# Data_Receiver.net
KiCad netlist of a schematic drawn in Altium Designer
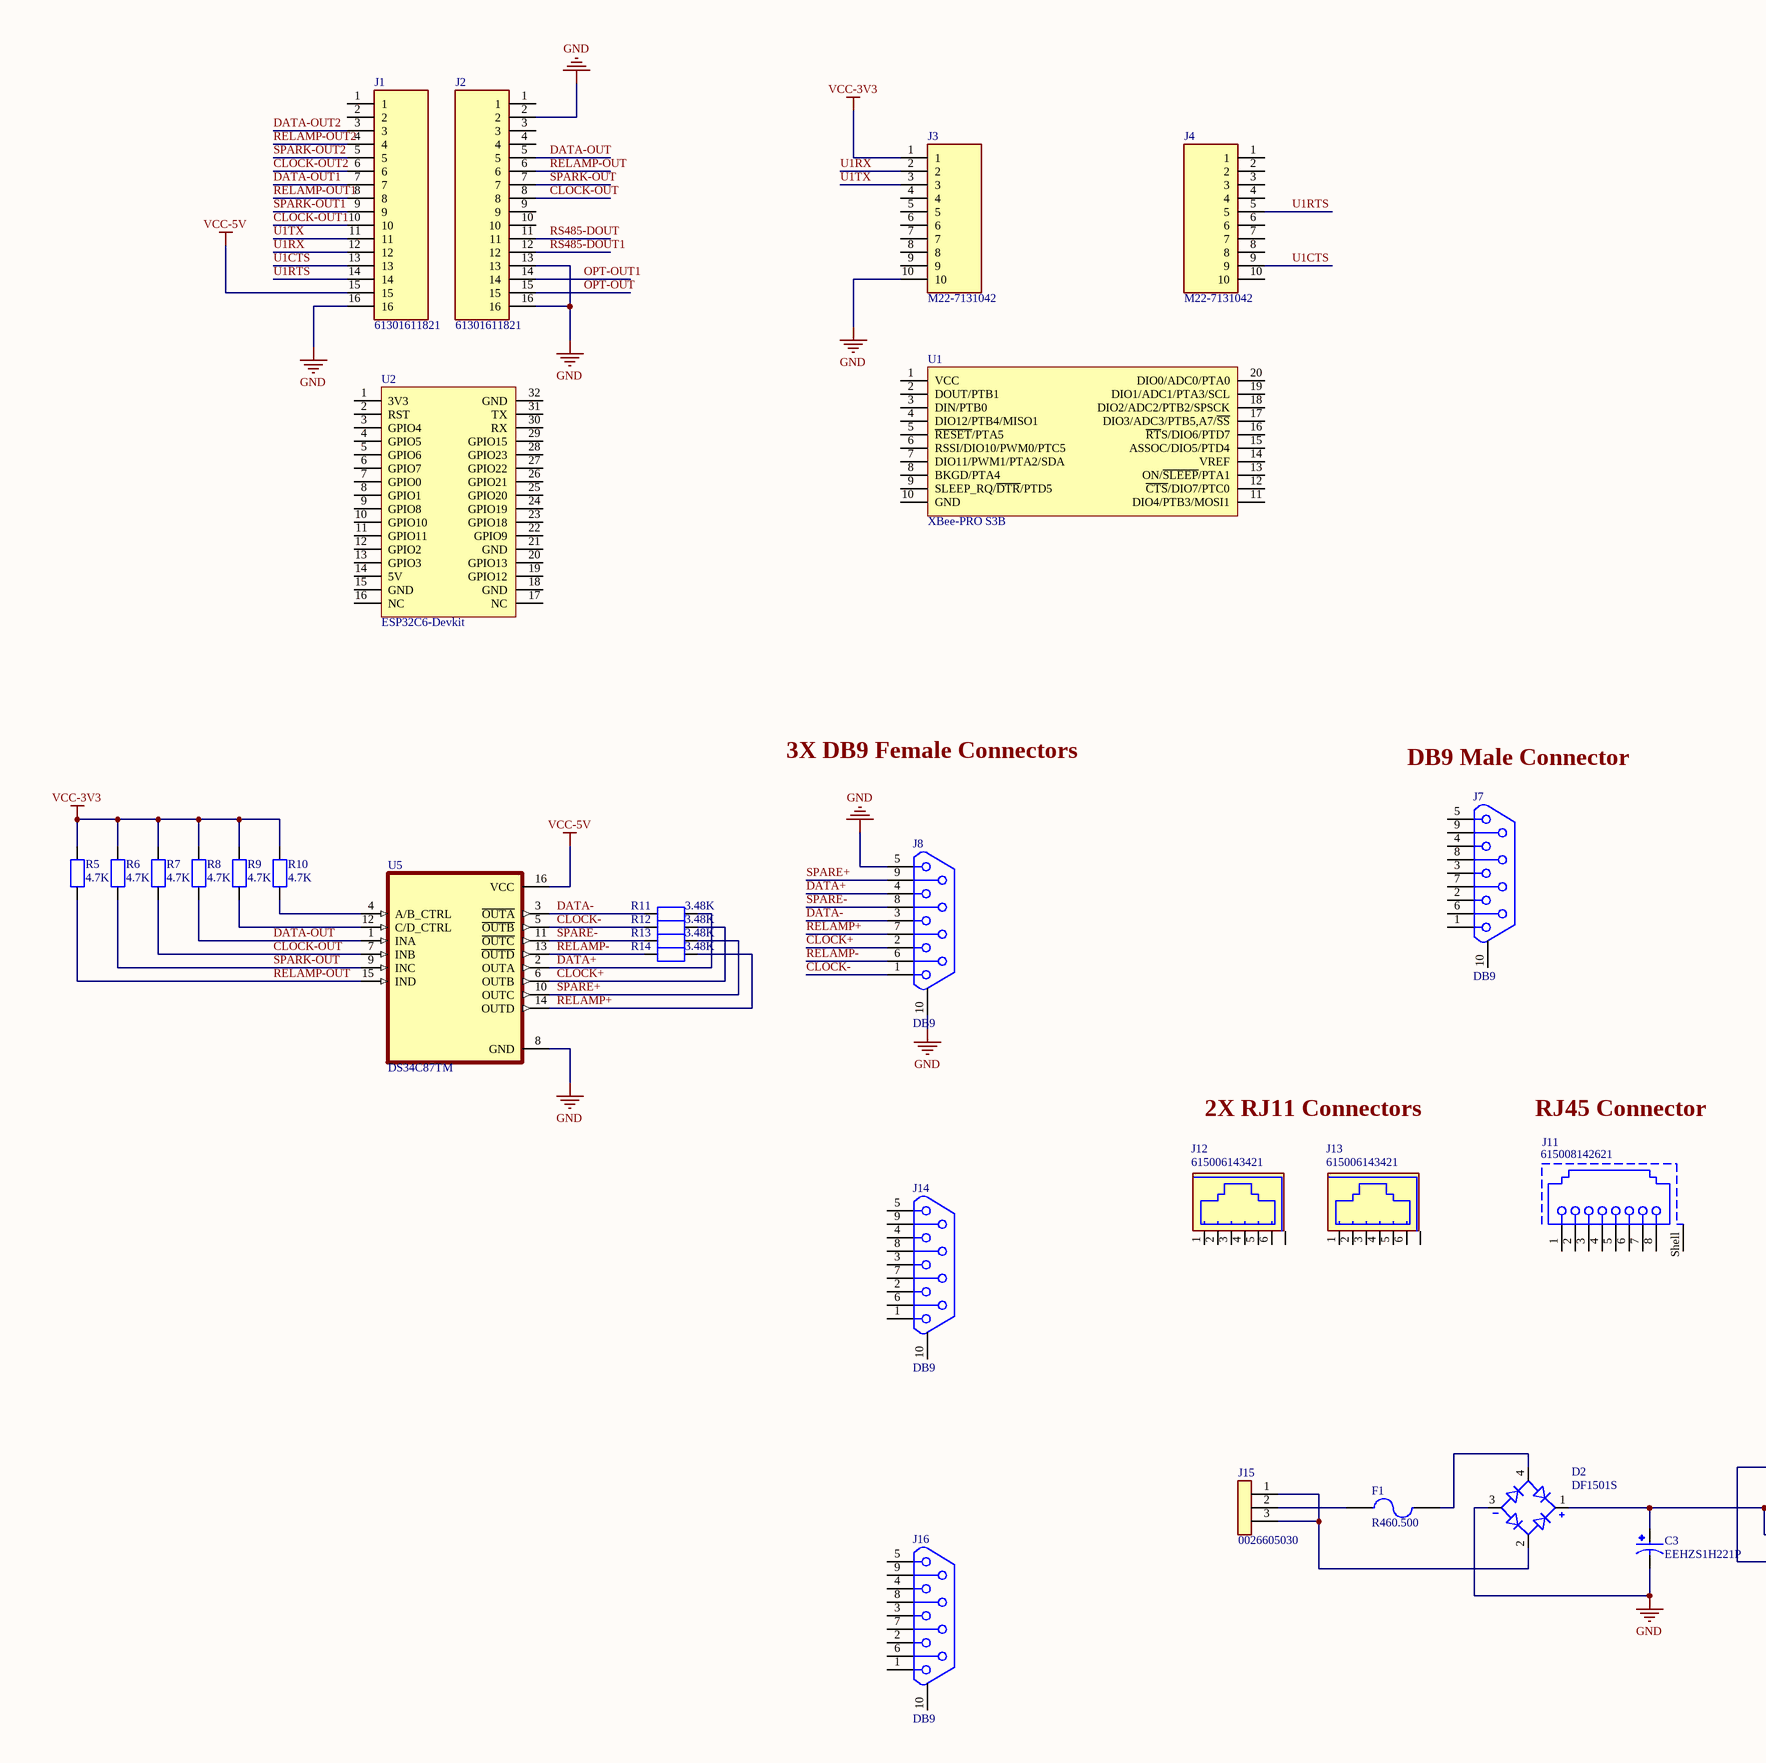
[diagram p0: Data Receiver.SchDoc, left]
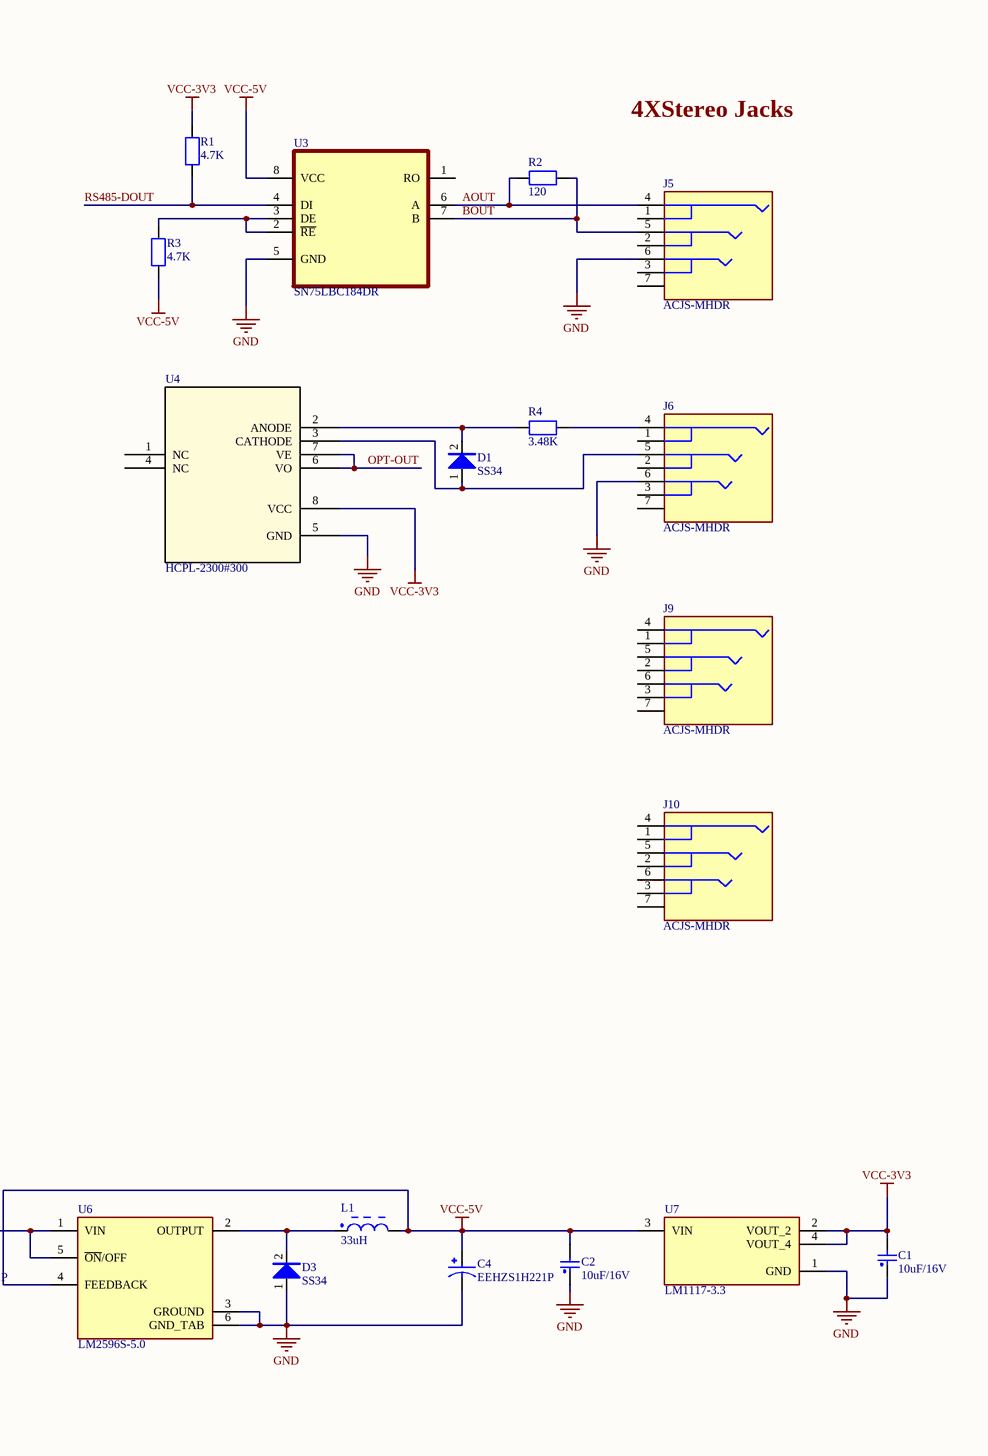
[diagram p1: Data Receiver.SchDoc, right]

(export (version "E")
  (design (tool "Eeschema 10.0.6"))
  (components
    (comp (ref "C1")
      (value "10uF/16V")
      (footprint "CAP-0805")
      (description "Capacitor")
      (fields
        (field (name "MANUFACTURER") "Samsung Electro-Mechanics")
        (field (name "MANUFACTURER PART NUMBER") "CL10B104KO8NNNC")
      )
      (libsource (lib "Data Receiver") (part "CAP"))
    )
    (comp (ref "C2")
      (value "10uF/16V")
      (footprint "CAP-0805")
      (description "Capacitor")
      (fields
        (field (name "MANUFACTURER") "Samsung Electro-Mechanics")
        (field (name "MANUFACTURER PART NUMBER") "CL10B104KO8NNNC")
      )
      (libsource (lib "Data Receiver") (part "CAP"))
    )
    (comp (ref "C3")
      (value "EEHZS1H221P")
      (footprint "CAP_EEHZS1H221P")
      (description "Aluminium Organic Polymer Capacitors 50VDC 220uF 125degC Hybrid Cap AEC-Q200")
      (fields
        (field (name "MANUFACTURER") "Panasonic")
        (field (name "MANUFACTURER PART NUMBER") "EEH-ZS1H221P")
      )
      (libsource (lib "Data Receiver") (part "EEHZS1H221P"))
    )
    (comp (ref "C4")
      (value "EEHZS1H221P")
      (footprint "CAP_EEHZS1H221P")
      (description "Aluminium Organic Polymer Capacitors 50VDC 220uF 125degC Hybrid Cap AEC-Q200")
      (fields
        (field (name "MANUFACTURER") "Panasonic")
        (field (name "MANUFACTURER PART NUMBER") "EEH-ZS1H221P")
      )
      (libsource (lib "Data Receiver") (part "EEHZS1H221P"))
    )
    (comp (ref "D1")
      (value "SS34")
      (footprint "SMA")
      (description "Diode 40 V 3A Surface Mount SMA")
      (fields (field (name "MANUFACTURER") "Taiwan Semiconductor"))
      (libsource (lib "Data Receiver") (part "DIODE"))
    )
    (comp (ref "D2")
      (value "DF1501S")
      (footprint "SOT520P1040X293-4N")
      (description "Bridge Rectifier Single Phase Standard 100V Surface Mount DFS")
      (fields (field (name "MANUFACTURER") "Diodes Incorporated"))
      (libsource (lib "Data Receiver") (part "DF1501S"))
    )
    (comp (ref "D3")
      (value "SS34")
      (footprint "SMA")
      (description "Diode 40 V 3A Surface Mount SMA")
      (fields (field (name "MANUFACTURER") "Taiwan Semiconductor"))
      (libsource (lib "Data Receiver") (part "DIODE"))
    )
    (comp (ref "F1")
      (value "R460.500")
      (footprint "CAPM7243X30N")
      (description "500 mA 125 V AC 125 V DC Fuse Board Mount (Cartridge Style Excluded) Surface Mount 2-SMD, J-Lead")
      (fields
        (field (name "MANUFACTURER") "Littelfuse Inc.")
        (field (name "MANUFACTURER PART NUMBER") "0460.500ER")
      )
      (libsource (lib "Data Receiver") (part "Fuse 2"))
    )
    (comp (ref "J1")
      (value "61301611821")
      (footprint "61301611821")
      (description "16 Position Header Connector 0.100\" (2.54mm) Through Hole Gold")
      (fields (field (name "MANUFACTURER") "Wurth Elektronik"))
      (libsource (lib "") (part "61301611821_1"))
    )
    (comp (ref "J2")
      (value "61301611821")
      (footprint "61301611821")
      (description "16 Position Header Connector 0.100\" (2.54mm) Through Hole Gold")
      (fields (field (name "MANUFACTURER") "Wurth Elektronik"))
      (libsource (lib "Data Receiver") (part "61301611821"))
    )
    (comp (ref "J3")
      (value "M22-7131042")
      (footprint "M22-7131042")
      (fields (field (name "MANUFACTURER") "Harwin"))
      (libsource (lib "Data Receiver") (part "M22-7131042"))
    )
    (comp (ref "J4")
      (value "M22-7131042")
      (footprint "M22-7131042")
      (fields (field (name "MANUFACTURER") "Harwin"))
      (libsource (lib "") (part "M22-7131042_1"))
    )
    (comp (ref "J5")
      (value "ACJS-MHDR")
      (footprint "ACJSMHDR")
      (description "Phone Connectors 1/4\" STEREO SWITCHED REAN")
      (fields (field (name "MANUFACTURER") "Amphenol Audio"))
      (libsource (lib "Data Receiver") (part "ACJS-MHDR"))
    )
    (comp (ref "J6")
      (value "ACJS-MHDR")
      (footprint "ACJSMHDR")
      (description "Phone Connectors 1/4\" STEREO SWITCHED REAN")
      (fields (field (name "MANUFACTURER") "Amphenol Audio"))
      (libsource (lib "Data Receiver") (part "ACJS-MHDR"))
    )
    (comp (ref "J7")
      (value "DB9")
      (footprint "DB9/F_A")
      (description "9 Position D-Sub Receptacle, Male Sockets Connector")
      (fields
        (field (name "MANUFACTURER") "Würth Elektronik")
        (field (name "MANUFACTURER PART NUMBER") "618009231321")
      )
      (libsource (lib "Data Receiver") (part "DB9_Male"))
    )
    (comp (ref "J8")
      (value "DB9")
      (footprint "DB9/S_A")
      (description "9 Position D-Sub Receptacle, Female Sockets Connector")
      (fields
        (field (name "MANUFACTURER") "Würth Elektronik")
        (field (name "MANUFACTURER PART NUMBER") "618009231321")
      )
      (libsource (lib "Data Receiver") (part "DB9"))
    )
    (comp (ref "J9")
      (value "ACJS-MHDR")
      (footprint "ACJSMHDR")
      (description "Phone Connectors 1/4\" STEREO SWITCHED REAN")
      (fields (field (name "MANUFACTURER") "Amphenol Audio"))
      (libsource (lib "Data Receiver") (part "ACJS-MHDR"))
    )
    (comp (ref "J10")
      (value "ACJS-MHDR")
      (footprint "ACJSMHDR")
      (description "Phone Connectors 1/4\" STEREO SWITCHED REAN")
      (fields (field (name "MANUFACTURER") "Amphenol Audio"))
      (libsource (lib "Data Receiver") (part "ACJS-MHDR"))
    )
    (comp (ref "J11")
      (value "615008142621")
      (footprint "615008142621")
      (description "WR-MJ Modular Jack THT Horizontal Shielded Rear Grounding Post 8P8C Tab Down")
      (fields (field (name "MANUFACTURER") "Wurth Elektronik"))
      (libsource (lib "Data Receiver") (part "615008142621"))
    )
    (comp (ref "J12")
      (value "615006143421")
      (footprint "615006143421")
      (description "Modular Connectors / Ethernet Connectors WR-COM Modular Jack Horztl 1.5A")
      (fields (field (name "MANUFACTURER") "Wurth Elektronik"))
      (libsource (lib "615006143421") (part "615006143421"))
    )
    (comp (ref "J13")
      (value "615006143421")
      (footprint "615006143421")
      (description "Modular Connectors / Ethernet Connectors WR-COM Modular Jack Horztl 1.5A")
      (fields (field (name "MANUFACTURER") "Wurth Elektronik"))
      (libsource (lib "615006143421") (part "615006143421"))
    )
    (comp (ref "J14")
      (value "DB9")
      (footprint "DB9/S_A")
      (description "9 Position D-Sub Receptacle, Female Sockets Connector")
      (fields
        (field (name "MANUFACTURER") "Würth Elektronik")
        (field (name "MANUFACTURER PART NUMBER") "618009231321")
      )
      (libsource (lib "Data Receiver") (part "DB9"))
    )
    (comp (ref "J15")
      (value "0026605030")
      (footprint "0026605030")
      (description "Connector Header Through Hole, Right Angle 3 position 0.156\" (3.96mm)")
      (fields (field (name "MANUFACTURER") "Molex"))
      (libsource (lib "Data Receiver") (part "HEADER3"))
    )
    (comp (ref "J16")
      (value "DB9")
      (footprint "DB9/S_A")
      (description "9 Position D-Sub Receptacle, Female Sockets Connector")
      (fields
        (field (name "MANUFACTURER") "Würth Elektronik")
        (field (name "MANUFACTURER PART NUMBER") "618009231321")
      )
      (libsource (lib "Data Receiver") (part "DB9"))
    )
    (comp (ref "L1")
      (value "33uH")
      (footprint "IND_BOURNS_SRR12")
      (description "33 µH Shielded Drum Core, Wirewound Inductor 3.5 A 57mOhm Max Nonstandard")
      (fields
        (field (name "MANUFACTURER") "Bourns Inc.")
        (field (name "MANUFACTURER PART NUMBER") "SRR1280-330M")
      )
      (libsource (lib "Data Receiver") (part "INDUCTOR"))
    )
    (comp (ref "R1")
      (value "4.7K")
      (footprint "R0603")
      (description "4.7 kOhms ±1% 0.1W, 1/10W Chip Resistor 0603 (1608 Metric) Moisture Resistant Thick Film")
      (fields
        (field (name "MANUFACTURER") "Yageo")
        (field (name "MANUFACTURER PART NUMBER") "RC0603FR-074K7L")
      )
      (libsource (lib "Data Receiver") (part "4.7K Ohms ±1% 0.1W"))
    )
    (comp (ref "R2")
      (value "120")
      (footprint "R0603")
      (description "120 Ohms ±1% 0.1W, 1/10W Chip Resistor 0603 (1608 Metric) Moisture Resistant Thick Film")
      (fields
        (field (name "MANUFACTURER") "Yageo")
        (field (name "MANUFACTURER PART NUMBER") "RC0603FR-07120RL")
      )
      (libsource (lib "Data Receiver") (part "120 Ohms ±1% 0.1W"))
    )
    (comp (ref "R3")
      (value "4.7K")
      (footprint "R0603")
      (description "4.7 kOhms ±1% 0.1W, 1/10W Chip Resistor 0603 (1608 Metric) Moisture Resistant Thick Film")
      (fields
        (field (name "MANUFACTURER") "Yageo")
        (field (name "MANUFACTURER PART NUMBER") "RC0603FR-074K7L")
      )
      (libsource (lib "Data Receiver") (part "4.7K Ohms ±1% 0.1W"))
    )
    (comp (ref "R4")
      (value "3.48K")
      (footprint "R0603")
      (description "3.48 kOhms ±1% 0.1W, 1/10W Chip Resistor 0603 (1608 Metric) Moisture Resistant Thick Film")
      (fields
        (field (name "MANUFACTURER") "Yageo")
        (field (name "MANUFACTURER PART NUMBER") "RC0603FR-073K48L")
      )
      (libsource (lib "Data Receiver") (part "3.48K Ohms ±1% 0.1W"))
    )
    (comp (ref "R5")
      (value "4.7K")
      (footprint "R0603")
      (description "4.7 kOhms ±1% 0.1W, 1/10W Chip Resistor 0603 (1608 Metric) Moisture Resistant Thick Film")
      (fields
        (field (name "MANUFACTURER") "Yageo")
        (field (name "MANUFACTURER PART NUMBER") "RC0603FR-074K7L")
      )
      (libsource (lib "Data Receiver") (part "4.7K Ohms ±1% 0.1W"))
    )
    (comp (ref "R6")
      (value "4.7K")
      (footprint "R0603")
      (description "4.7 kOhms ±1% 0.1W, 1/10W Chip Resistor 0603 (1608 Metric) Moisture Resistant Thick Film")
      (fields
        (field (name "MANUFACTURER") "Yageo")
        (field (name "MANUFACTURER PART NUMBER") "RC0603FR-074K7L")
      )
      (libsource (lib "Data Receiver") (part "4.7K Ohms ±1% 0.1W"))
    )
    (comp (ref "R7")
      (value "4.7K")
      (footprint "R0603")
      (description "4.7 kOhms ±1% 0.1W, 1/10W Chip Resistor 0603 (1608 Metric) Moisture Resistant Thick Film")
      (fields
        (field (name "MANUFACTURER") "Yageo")
        (field (name "MANUFACTURER PART NUMBER") "RC0603FR-074K7L")
      )
      (libsource (lib "Data Receiver") (part "4.7K Ohms ±1% 0.1W"))
    )
    (comp (ref "R8")
      (value "4.7K")
      (footprint "R0603")
      (description "4.7 kOhms ±1% 0.1W, 1/10W Chip Resistor 0603 (1608 Metric) Moisture Resistant Thick Film")
      (fields
        (field (name "MANUFACTURER") "Yageo")
        (field (name "MANUFACTURER PART NUMBER") "RC0603FR-074K7L")
      )
      (libsource (lib "Data Receiver") (part "4.7K Ohms ±1% 0.1W"))
    )
    (comp (ref "R9")
      (value "4.7K")
      (footprint "R0603")
      (description "4.7 kOhms ±1% 0.1W, 1/10W Chip Resistor 0603 (1608 Metric) Moisture Resistant Thick Film")
      (fields
        (field (name "MANUFACTURER") "Yageo")
        (field (name "MANUFACTURER PART NUMBER") "RC0603FR-074K7L")
      )
      (libsource (lib "Data Receiver") (part "4.7K Ohms ±1% 0.1W"))
    )
    (comp (ref "R10")
      (value "4.7K")
      (footprint "R0603")
      (description "4.7 kOhms ±1% 0.1W, 1/10W Chip Resistor 0603 (1608 Metric) Moisture Resistant Thick Film")
      (fields
        (field (name "MANUFACTURER") "Yageo")
        (field (name "MANUFACTURER PART NUMBER") "RC0603FR-074K7L")
      )
      (libsource (lib "Data Receiver") (part "4.7K Ohms ±1% 0.1W"))
    )
    (comp (ref "R11")
      (value "3.48K")
      (footprint "R0603")
      (description "3.48 kOhms ±1% 0.1W, 1/10W Chip Resistor 0603 (1608 Metric) Moisture Resistant Thick Film")
      (fields
        (field (name "MANUFACTURER") "Yageo")
        (field (name "MANUFACTURER PART NUMBER") "RC0603FR-073K48L")
      )
      (libsource (lib "Data Receiver") (part "3.48K Ohms ±1% 0.1W"))
    )
    (comp (ref "R12")
      (value "3.48K")
      (footprint "R0603")
      (description "3.48 kOhms ±1% 0.1W, 1/10W Chip Resistor 0603 (1608 Metric) Moisture Resistant Thick Film")
      (fields
        (field (name "MANUFACTURER") "Yageo")
        (field (name "MANUFACTURER PART NUMBER") "RC0603FR-073K48L")
      )
      (libsource (lib "Data Receiver") (part "3.48K Ohms ±1% 0.1W"))
    )
    (comp (ref "R13")
      (value "3.48K")
      (footprint "R0603")
      (description "3.48 kOhms ±1% 0.1W, 1/10W Chip Resistor 0603 (1608 Metric) Moisture Resistant Thick Film")
      (fields
        (field (name "MANUFACTURER") "Yageo")
        (field (name "MANUFACTURER PART NUMBER") "RC0603FR-073K48L")
      )
      (libsource (lib "Data Receiver") (part "3.48K Ohms ±1% 0.1W"))
    )
    (comp (ref "R14")
      (value "3.48K")
      (footprint "R0603")
      (description "3.48 kOhms ±1% 0.1W, 1/10W Chip Resistor 0603 (1608 Metric) Moisture Resistant Thick Film")
      (fields
        (field (name "MANUFACTURER") "Yageo")
        (field (name "MANUFACTURER PART NUMBER") "RC0603FR-073K48L")
      )
      (libsource (lib "Data Receiver") (part "3.48K Ohms ±1% 0.1W"))
    )
    (comp (ref "U1")
      (value "XBee-PRO S3B")
      (footprint "XBEE(MMS-110-02-L-SV-K-TR)")
      (description "General ISM < 1GHz Transceiver Module 920MHz Antenna Not Included, RP-SMA Through Hole")
      (fields (field (name "MANUFACTURER") "DIGI") (field (name "MANUFACTURER PART NUMBER") "XBP9B-XCST-022"))
      (libsource (lib "Data Receiver") (part "XBee-PRO S3B"))
    )
    (comp (ref "U2")
      (value "ESP32C6-Devkit")
      (footprint "ESP32-C6-Devkit")
      (description "ESP32-C6-MINI-1 Transceiver; Bluetooth® 5 2.4GHz Evaluation Board")
      (fields
        (field (name "MANUFACTURER") "Espressif Systems")
        (field (name "MANUFACTURER PART NUMBER") "ESP32-C6-DevKitM-1-N4")
      )
      (libsource (lib "Data Receiver") (part "ESP32C6-Devkit"))
    )
    (comp (ref "U3")
      (value "SN75LBC184DR")
      (footprint "SOIC127P620X175-8N")
      (description "Enhanced Low Power Half-Duplex RS-485 Transceivers")
      (fields
        (field (name "MANUFACTURER") "MaxLinear, Inc.")
        (field (name "MANUFACTURER PART NUMBER") "SP485EEN-L")
      )
      (libsource (lib "Data Receiver") (part "SP485EEN-L"))
    )
    (comp (ref "U4")
      (value "HCPL-2300#300")
      (footprint "SOP254P960X420-8N")
      (fields (field (name "MANUFACTURER") "Broadcom Limited"))
      (libsource (lib "Data Receiver") (part "HCPL-2300#300"))
    )
    (comp (ref "U5")
      (value "DS34C87TM")
      (footprint "SOIC127P600X175-16N")
      (description "4/0 Driver RS422, RS485 16-SOIC")
      (fields
        (field (name "MANUFACTURER") "Texas Instruments")
        (field (name "MANUFACTURER PART NUMBER") "DS34C87TM/NOPB")
      )
      (libsource (lib "Data Receiver") (part "DS34C87TM"))
    )
    (comp (ref "U6")
      (value "LM2596S-5.0")
      (footprint "TO170P1524X483-6N")
      (description "IC REG BUCK 5V 3A TO263-5")
      (fields (field (name "MANUFACTURER") "Texas Instruments"))
      (libsource (lib "Data Receiver") (part "LM2596S-5.0"))
    )
    (comp (ref "U7")
      (value "LM1117-3.3")
      (footprint "VREG_LM1117MPX-3.3")
      (description "800-mA 15-V linear voltage regulator 4-SOT-223 0 to 125")
      (fields
        (field (name "MANUFACTURER") "National Semiconductor")
        (field (name "MANUFACTURER PART NUMBER") "LM1117MPX-3.3")
      )
      (libsource (lib "Data Receiver") (part "LM1117MPX-3.3"))
    )
  )
  (nets
    (net (code "1") (name "/AOUT") (class "Default")
      (node (ref "J5") (pin "4") (pinfunction "4_4") (pintype "passive"))
      (node (ref "R2") (pin "2") (pinfunction "2_2") (pintype "passive"))
      (node (ref "U3") (pin "6") (pinfunction "A_6") (pintype "passive"))
    )
    (net (code "2") (name "/BOUT") (class "Default")
      (node (ref "J5") (pin "5") (pinfunction "5_5") (pintype "passive"))
      (node (ref "R2") (pin "1") (pinfunction "1_1") (pintype "passive"))
      (node (ref "U3") (pin "7") (pinfunction "B_7") (pintype "passive"))
    )
    (net (code "3") (name "/CLOCK+") (class "Default")
      (node (ref "J8") (pin "2") (pinfunction "2_2") (pintype "passive"))
      (node (ref "R12") (pin "2") (pinfunction "2_2") (pintype "passive"))
      (node (ref "U5") (pin "6") (pinfunction "OUTB_6") (pintype "output"))
    )
    (net (code "4") (name "/CLOCK-") (class "Default")
      (node (ref "J8") (pin "1") (pinfunction "1_1") (pintype "passive"))
      (node (ref "R12") (pin "1") (pinfunction "1_1") (pintype "passive"))
      (node (ref "U5") (pin "5") (pinfunction "~{OUTB}_5") (pintype "output"))
    )
    (net (code "5") (name "/CLOCK-OUT") (class "Default")
      (node (ref "J2") (pin "8") (pinfunction "8_8") (pintype "passive"))
      (node (ref "R7") (pin "1") (pinfunction "1_1") (pintype "passive"))
      (node (ref "U5") (pin "7") (pinfunction "INB_7") (pintype "input"))
    )
    (net (code "6") (name "/CLOCK-OUT1") (class "Default")
      (node (ref "J1") (pin "10") (pinfunction "10_10") (pintype "passive"))
    )
    (net (code "7") (name "/CLOCK-OUT2") (class "Default")
      (node (ref "J1") (pin "6") (pinfunction "6_6") (pintype "passive"))
    )
    (net (code "8") (name "/DATA+") (class "Default")
      (node (ref "J8") (pin "4") (pinfunction "4_4") (pintype "passive"))
      (node (ref "R11") (pin "2") (pinfunction "2_2") (pintype "passive"))
      (node (ref "U5") (pin "2") (pinfunction "OUTA_2") (pintype "output"))
    )
    (net (code "9") (name "/DATA-") (class "Default")
      (node (ref "J8") (pin "3") (pinfunction "3_3") (pintype "passive"))
      (node (ref "R11") (pin "1") (pinfunction "1_1") (pintype "passive"))
      (node (ref "U5") (pin "3") (pinfunction "~{OUTA}_3") (pintype "output"))
    )
    (net (code "10") (name "/DATA-OUT") (class "Default")
      (node (ref "J2") (pin "5") (pinfunction "5_5") (pintype "passive"))
      (node (ref "R8") (pin "1") (pinfunction "1_1") (pintype "passive"))
      (node (ref "U5") (pin "1") (pinfunction "INA_1") (pintype "input"))
    )
    (net (code "11") (name "/DATA-OUT1") (class "Default")
      (node (ref "J1") (pin "7") (pinfunction "7_7") (pintype "passive"))
    )
    (net (code "12") (name "/DATA-OUT2") (class "Default")
      (node (ref "J1") (pin "3") (pinfunction "3_3") (pintype "passive"))
    )
    (net (code "13") (name "/OPT-OUT") (class "Default")
      (node (ref "J2") (pin "15") (pinfunction "15_15") (pintype "passive"))
      (node (ref "U4") (pin "6") (pinfunction "VO_6") (pintype "passive"))
      (node (ref "U4") (pin "7") (pinfunction "VE_7") (pintype "passive"))
    )
    (net (code "14") (name "/OPT-OUT1") (class "Default")
      (node (ref "J2") (pin "14") (pinfunction "14_14") (pintype "passive"))
    )
    (net (code "15") (name "/RELAMP+") (class "Default")
      (node (ref "J8") (pin "7") (pinfunction "7_7") (pintype "passive"))
      (node (ref "R14") (pin "2") (pinfunction "2_2") (pintype "passive"))
      (node (ref "U5") (pin "14") (pinfunction "OUTD_14") (pintype "output"))
    )
    (net (code "16") (name "/RELAMP-") (class "Default")
      (node (ref "J8") (pin "6") (pinfunction "6_6") (pintype "passive"))
      (node (ref "R14") (pin "1") (pinfunction "1_1") (pintype "passive"))
      (node (ref "U5") (pin "13") (pinfunction "~{OUTD}_13") (pintype "output"))
    )
    (net (code "17") (name "/RELAMP-OUT") (class "Default")
      (node (ref "J2") (pin "6") (pinfunction "6_6") (pintype "passive"))
      (node (ref "R5") (pin "1") (pinfunction "1_1") (pintype "passive"))
      (node (ref "U5") (pin "15") (pinfunction "IND_15") (pintype "input"))
    )
    (net (code "18") (name "/RELAMP-OUT1") (class "Default")
      (node (ref "J1") (pin "8") (pinfunction "8_8") (pintype "passive"))
    )
    (net (code "19") (name "/RELAMP-OUT2") (class "Default")
      (node (ref "J1") (pin "4") (pinfunction "4_4") (pintype "passive"))
    )
    (net (code "20") (name "/RS485-DOUT") (class "Default")
      (node (ref "J2") (pin "11") (pinfunction "11_11") (pintype "passive"))
      (node (ref "R1") (pin "1") (pinfunction "1_1") (pintype "passive"))
      (node (ref "U3") (pin "4") (pinfunction "DI_4") (pintype "passive"))
    )
    (net (code "21") (name "/RS485-DOUT1") (class "Default")
      (node (ref "J2") (pin "12") (pinfunction "12_12") (pintype "passive"))
    )
    (net (code "22") (name "/SPARE+") (class "Default")
      (node (ref "J8") (pin "9") (pinfunction "9_9") (pintype "passive"))
      (node (ref "R13") (pin "2") (pinfunction "2_2") (pintype "passive"))
      (node (ref "U5") (pin "10") (pinfunction "OUTC_10") (pintype "output"))
    )
    (net (code "23") (name "/SPARE-") (class "Default")
      (node (ref "J8") (pin "8") (pinfunction "8_8") (pintype "passive"))
      (node (ref "R13") (pin "1") (pinfunction "1_1") (pintype "passive"))
      (node (ref "U5") (pin "11") (pinfunction "~{OUTC}_11") (pintype "output"))
    )
    (net (code "24") (name "/SPARK-OUT") (class "Default")
      (node (ref "J2") (pin "7") (pinfunction "7_7") (pintype "passive"))
      (node (ref "R6") (pin "1") (pinfunction "1_1") (pintype "passive"))
      (node (ref "U5") (pin "9") (pinfunction "INC_9") (pintype "input"))
    )
    (net (code "25") (name "/SPARK-OUT1") (class "Default")
      (node (ref "J1") (pin "9") (pinfunction "9_9") (pintype "passive"))
    )
    (net (code "26") (name "/SPARK-OUT2") (class "Default")
      (node (ref "J1") (pin "5") (pinfunction "5_5") (pintype "passive"))
    )
    (net (code "27") (name "/U1CTS") (class "Default")
      (node (ref "J1") (pin "13") (pinfunction "13_13") (pintype "passive"))
      (node (ref "J4") (pin "9") (pinfunction "9_9") (pintype "passive"))
    )
    (net (code "28") (name "/U1RTS") (class "Default")
      (node (ref "J1") (pin "14") (pinfunction "14_14") (pintype "passive"))
      (node (ref "J4") (pin "5") (pinfunction "5_5") (pintype "passive"))
    )
    (net (code "29") (name "/U1RX") (class "Default")
      (node (ref "J1") (pin "12") (pinfunction "12_12") (pintype "passive"))
      (node (ref "J3") (pin "2") (pinfunction "2_2") (pintype "passive"))
    )
    (net (code "30") (name "/U1TX") (class "Default")
      (node (ref "J1") (pin "11") (pinfunction "11_11") (pintype "passive"))
      (node (ref "J3") (pin "3") (pinfunction "3_3") (pintype "passive"))
    )
    (net (code "31") (name "GND") (class "Default")
      (node (ref "C1") (pin "1") (pinfunction "1_1") (pintype "passive"))
      (node (ref "C2") (pin "1") (pinfunction "1_1") (pintype "passive"))
      (node (ref "C3") (pin "2") (pinfunction "2_2") (pintype "passive"))
      (node (ref "C4") (pin "2") (pinfunction "2_2") (pintype "passive"))
      (node (ref "D2") (pin "3") (pinfunction "NEG_3") (pintype "passive"))
      (node (ref "D3") (pin "1") (pinfunction "1_1") (pintype "passive"))
      (node (ref "J1") (pin "16") (pinfunction "16_16") (pintype "passive"))
      (node (ref "J2") (pin "13") (pinfunction "13_13") (pintype "passive"))
      (node (ref "J2") (pin "16") (pinfunction "16_16") (pintype "passive"))
      (node (ref "J2") (pin "2") (pinfunction "2_2") (pintype "passive"))
      (node (ref "J3") (pin "10") (pinfunction "10_10") (pintype "passive"))
      (node (ref "J5") (pin "6") (pinfunction "6_6") (pintype "passive"))
      (node (ref "J6") (pin "6") (pinfunction "6_6") (pintype "passive"))
      (node (ref "J8") (pin "10") (pinfunction "10_10") (pintype "passive"))
      (node (ref "J8") (pin "5") (pinfunction "5_5") (pintype "passive"))
      (node (ref "U3") (pin "5") (pinfunction "GND_5") (pintype "passive"))
      (node (ref "U4") (pin "5") (pinfunction "GND_5") (pintype "power_in"))
      (node (ref "U5") (pin "8") (pinfunction "GND_8") (pintype "power_in"))
      (node (ref "U6") (pin "3") (pinfunction "GROUND_3") (pintype "passive"))
      (node (ref "U6") (pin "6") (pinfunction "GND_TAB_6") (pintype "passive"))
      (node (ref "U7") (pin "1") (pinfunction "GND_1") (pintype "passive"))
    )
    (net (code "32") (name "Net-(D2-AC1)") (class "Default")
      (node (ref "D2") (pin "2") (pinfunction "AC1_2") (pintype "passive"))
      (node (ref "J15") (pin "1") (pintype "passive"))
      (node (ref "J15") (pin "3") (pintype "passive"))
    )
    (net (code "33") (name "Net-(D2-AC2)") (class "Default")
      (node (ref "D2") (pin "4") (pinfunction "AC2_4") (pintype "passive"))
      (node (ref "F1") (pin "2") (pinfunction "2_2") (pintype "passive"))
    )
    (net (code "34") (name "Net-(D2-POS)") (class "Default")
      (node (ref "C3") (pin "1") (pinfunction "1_1") (pintype "passive"))
      (node (ref "D2") (pin "1") (pinfunction "POS_1") (pintype "passive"))
      (node (ref "U6") (pin "1") (pinfunction "VIN_1") (pintype "passive"))
      (node (ref "U6") (pin "5") (pinfunction "~{ON}/OFF_5") (pintype "passive"))
    )
    (net (code "35") (name "Net-(F1-Pad1)") (class "Default")
      (node (ref "F1") (pin "1") (pinfunction "1_1") (pintype "passive"))
      (node (ref "J15") (pin "2") (pintype "passive"))
    )
    (net (code "36") (name "Net-(J6-Pad4)") (class "Default")
      (node (ref "J6") (pin "4") (pinfunction "4_4") (pintype "passive"))
      (node (ref "R4") (pin "2") (pinfunction "2_2") (pintype "passive"))
    )
    (net (code "37") (name "Net-(J12-SHIELD-PadS1)") (class "Default")
      (node (ref "J12") (pin "S1") (pinfunction "SHIELD_S1") (pintype "passive"))
      (node (ref "J12") (pin "S2") (pinfunction "SHIELD_S2") (pintype "passive"))
    )
    (net (code "38") (name "Net-(J13-SHIELD-PadS1)") (class "Default")
      (node (ref "J13") (pin "S1") (pinfunction "SHIELD_S1") (pintype "passive"))
      (node (ref "J13") (pin "S2") (pinfunction "SHIELD_S2") (pintype "passive"))
    )
    (net (code "39") (name "Net-(U3-DE)") (class "Default")
      (node (ref "R3") (pin "2") (pinfunction "2_2") (pintype "passive"))
      (node (ref "U3") (pin "2") (pinfunction "~{RE}_2") (pintype "passive"))
      (node (ref "U3") (pin "3") (pinfunction "DE_3") (pintype "passive"))
    )
    (net (code "40") (name "Net-(U4-ANODE)") (class "Default")
      (node (ref "D1") (pin "2") (pinfunction "2_2") (pintype "passive"))
      (node (ref "R4") (pin "1") (pinfunction "1_1") (pintype "passive"))
      (node (ref "U4") (pin "2") (pinfunction "ANODE_2") (pintype "passive"))
    )
    (net (code "41") (name "Net-(U4-CATHODE)") (class "Default")
      (node (ref "D1") (pin "1") (pinfunction "1_1") (pintype "passive"))
      (node (ref "J6") (pin "5") (pinfunction "5_5") (pintype "passive"))
      (node (ref "U4") (pin "3") (pinfunction "CATHODE_3") (pintype "passive"))
    )
    (net (code "42") (name "Net-(U5-A{slash}B_CTRL)") (class "Default")
      (node (ref "R10") (pin "1") (pinfunction "1_1") (pintype "passive"))
      (node (ref "U5") (pin "4") (pinfunction "A/B_CTRL_4") (pintype "input"))
    )
    (net (code "43") (name "Net-(U5-C{slash}D_CTRL)") (class "Default")
      (node (ref "R9") (pin "1") (pinfunction "1_1") (pintype "passive"))
      (node (ref "U5") (pin "12") (pinfunction "C/D_CTRL_12") (pintype "input"))
    )
    (net (code "44") (name "Net-(U6-OUTPUT)") (class "Default")
      (node (ref "D3") (pin "2") (pinfunction "2_2") (pintype "passive"))
      (node (ref "L1") (pin "1") (pinfunction "1_1") (pintype "passive"))
      (node (ref "U6") (pin "2") (pinfunction "OUTPUT_2") (pintype "passive"))
    )
    (net (code "45") (name "VCC-3V3") (class "Default")
      (node (ref "C1") (pin "2") (pinfunction "2_2") (pintype "passive"))
      (node (ref "J3") (pin "1") (pinfunction "1_1") (pintype "passive"))
      (node (ref "R1") (pin "2") (pinfunction "2_2") (pintype "passive"))
      (node (ref "R10") (pin "2") (pinfunction "2_2") (pintype "passive"))
      (node (ref "R5") (pin "2") (pinfunction "2_2") (pintype "passive"))
      (node (ref "R6") (pin "2") (pinfunction "2_2") (pintype "passive"))
      (node (ref "R7") (pin "2") (pinfunction "2_2") (pintype "passive"))
      (node (ref "R8") (pin "2") (pinfunction "2_2") (pintype "passive"))
      (node (ref "R9") (pin "2") (pinfunction "2_2") (pintype "passive"))
      (node (ref "U4") (pin "8") (pinfunction "VCC_8") (pintype "power_in"))
      (node (ref "U7") (pin "2") (pinfunction "VOUT_2_2") (pintype "passive"))
      (node (ref "U7") (pin "4") (pinfunction "VOUT_4_4") (pintype "passive"))
    )
    (net (code "46") (name "VCC-5V") (class "Default")
      (node (ref "C2") (pin "2") (pinfunction "2_2") (pintype "passive"))
      (node (ref "C4") (pin "1") (pinfunction "1_1") (pintype "passive"))
      (node (ref "J1") (pin "15") (pinfunction "15_15") (pintype "passive"))
      (node (ref "L1") (pin "2") (pinfunction "2_2") (pintype "passive"))
      (node (ref "R3") (pin "1") (pinfunction "1_1") (pintype "passive"))
      (node (ref "U3") (pin "8") (pinfunction "VCC_8") (pintype "passive"))
      (node (ref "U5") (pin "16") (pinfunction "VCC_16") (pintype "power_in"))
      (node (ref "U6") (pin "4") (pinfunction "FEEDBACK_4") (pintype "passive"))
      (node (ref "U7") (pin "3") (pinfunction "VIN_3") (pintype "passive"))
    )
    (net (code "47") (name "unconnected-(J1-Pad1)") (class "Default")
      (node (ref "J1") (pin "1") (pinfunction "1_1") (pintype "passive"))
    )
    (net (code "48") (name "unconnected-(J1-Pad2)") (class "Default")
      (node (ref "J1") (pin "2") (pinfunction "2_2") (pintype "passive"))
    )
    (net (code "49") (name "unconnected-(J2-Pad1)") (class "Default")
      (node (ref "J2") (pin "1") (pinfunction "1_1") (pintype "passive"))
    )
    (net (code "50") (name "unconnected-(J2-Pad3)") (class "Default")
      (node (ref "J2") (pin "3") (pinfunction "3_3") (pintype "passive"))
    )
    (net (code "51") (name "unconnected-(J2-Pad4)") (class "Default")
      (node (ref "J2") (pin "4") (pinfunction "4_4") (pintype "passive"))
    )
    (net (code "52") (name "unconnected-(J2-Pad9)") (class "Default")
      (node (ref "J2") (pin "9") (pinfunction "9_9") (pintype "passive"))
    )
    (net (code "53") (name "unconnected-(J2-Pad10)") (class "Default")
      (node (ref "J2") (pin "10") (pinfunction "10_10") (pintype "passive"))
    )
    (net (code "54") (name "unconnected-(J3-Pad4)") (class "Default")
      (node (ref "J3") (pin "4") (pinfunction "4_4") (pintype "passive"))
    )
    (net (code "55") (name "unconnected-(J3-Pad5)") (class "Default")
      (node (ref "J3") (pin "5") (pinfunction "5_5") (pintype "passive"))
    )
    (net (code "56") (name "unconnected-(J3-Pad6)") (class "Default")
      (node (ref "J3") (pin "6") (pinfunction "6_6") (pintype "passive"))
    )
    (net (code "57") (name "unconnected-(J3-Pad7)") (class "Default")
      (node (ref "J3") (pin "7") (pinfunction "7_7") (pintype "passive"))
    )
    (net (code "58") (name "unconnected-(J3-Pad8)") (class "Default")
      (node (ref "J3") (pin "8") (pinfunction "8_8") (pintype "passive"))
    )
    (net (code "59") (name "unconnected-(J3-Pad9)") (class "Default")
      (node (ref "J3") (pin "9") (pinfunction "9_9") (pintype "passive"))
    )
    (net (code "60") (name "unconnected-(J4-Pad1)") (class "Default")
      (node (ref "J4") (pin "1") (pinfunction "1_1") (pintype "passive"))
    )
    (net (code "61") (name "unconnected-(J4-Pad2)") (class "Default")
      (node (ref "J4") (pin "2") (pinfunction "2_2") (pintype "passive"))
    )
    (net (code "62") (name "unconnected-(J4-Pad3)") (class "Default")
      (node (ref "J4") (pin "3") (pinfunction "3_3") (pintype "passive"))
    )
    (net (code "63") (name "unconnected-(J4-Pad4)") (class "Default")
      (node (ref "J4") (pin "4") (pinfunction "4_4") (pintype "passive"))
    )
    (net (code "64") (name "unconnected-(J4-Pad6)") (class "Default")
      (node (ref "J4") (pin "6") (pinfunction "6_6") (pintype "passive"))
    )
    (net (code "65") (name "unconnected-(J4-Pad7)") (class "Default")
      (node (ref "J4") (pin "7") (pinfunction "7_7") (pintype "passive"))
    )
    (net (code "66") (name "unconnected-(J4-Pad8)") (class "Default")
      (node (ref "J4") (pin "8") (pinfunction "8_8") (pintype "passive"))
    )
    (net (code "67") (name "unconnected-(J4-Pad10)") (class "Default")
      (node (ref "J4") (pin "10") (pinfunction "10_10") (pintype "passive"))
    )
    (net (code "68") (name "unconnected-(J5-Pad1)") (class "Default")
      (node (ref "J5") (pin "1") (pinfunction "1_1") (pintype "passive"))
    )
    (net (code "69") (name "unconnected-(J5-Pad2)") (class "Default")
      (node (ref "J5") (pin "2") (pinfunction "2_2") (pintype "passive"))
    )
    (net (code "70") (name "unconnected-(J5-Pad3)") (class "Default")
      (node (ref "J5") (pin "3") (pinfunction "3_3") (pintype "passive"))
    )
    (net (code "71") (name "unconnected-(J5-Pad7)") (class "Default")
      (node (ref "J5") (pin "7") (pinfunction "7_7") (pintype "passive"))
    )
    (net (code "72") (name "unconnected-(J6-Pad1)") (class "Default")
      (node (ref "J6") (pin "1") (pinfunction "1_1") (pintype "passive"))
    )
    (net (code "73") (name "unconnected-(J6-Pad2)") (class "Default")
      (node (ref "J6") (pin "2") (pinfunction "2_2") (pintype "passive"))
    )
    (net (code "74") (name "unconnected-(J6-Pad3)") (class "Default")
      (node (ref "J6") (pin "3") (pinfunction "3_3") (pintype "passive"))
    )
    (net (code "75") (name "unconnected-(J6-Pad7)") (class "Default")
      (node (ref "J6") (pin "7") (pinfunction "7_7") (pintype "passive"))
    )
    (net (code "76") (name "unconnected-(J7-Pad1)") (class "Default")
      (node (ref "J7") (pin "1") (pinfunction "1_1") (pintype "passive"))
    )
    (net (code "77") (name "unconnected-(J7-Pad2)") (class "Default")
      (node (ref "J7") (pin "2") (pinfunction "2_2") (pintype "passive"))
    )
    (net (code "78") (name "unconnected-(J7-Pad3)") (class "Default")
      (node (ref "J7") (pin "3") (pinfunction "3_3") (pintype "passive"))
    )
    (net (code "79") (name "unconnected-(J7-Pad4)") (class "Default")
      (node (ref "J7") (pin "4") (pinfunction "4_4") (pintype "passive"))
    )
    (net (code "80") (name "unconnected-(J7-Pad5)") (class "Default")
      (node (ref "J7") (pin "5") (pinfunction "5_5") (pintype "passive"))
    )
    (net (code "81") (name "unconnected-(J7-Pad6)") (class "Default")
      (node (ref "J7") (pin "6") (pinfunction "6_6") (pintype "passive"))
    )
    (net (code "82") (name "unconnected-(J7-Pad7)") (class "Default")
      (node (ref "J7") (pin "7") (pinfunction "7_7") (pintype "passive"))
    )
    (net (code "83") (name "unconnected-(J7-Pad8)") (class "Default")
      (node (ref "J7") (pin "8") (pinfunction "8_8") (pintype "passive"))
    )
    (net (code "84") (name "unconnected-(J7-Pad9)") (class "Default")
      (node (ref "J7") (pin "9") (pinfunction "9_9") (pintype "passive"))
    )
    (net (code "85") (name "unconnected-(J7-Pad10)") (class "Default")
      (node (ref "J7") (pin "10") (pinfunction "10_10") (pintype "passive"))
    )
    (net (code "86") (name "unconnected-(J9-Pad1)") (class "Default")
      (node (ref "J9") (pin "1") (pinfunction "1_1") (pintype "passive"))
    )
    (net (code "87") (name "unconnected-(J9-Pad2)") (class "Default")
      (node (ref "J9") (pin "2") (pinfunction "2_2") (pintype "passive"))
    )
    (net (code "88") (name "unconnected-(J9-Pad3)") (class "Default")
      (node (ref "J9") (pin "3") (pinfunction "3_3") (pintype "passive"))
    )
    (net (code "89") (name "unconnected-(J9-Pad4)") (class "Default")
      (node (ref "J9") (pin "4") (pinfunction "4_4") (pintype "passive"))
    )
    (net (code "90") (name "unconnected-(J9-Pad5)") (class "Default")
      (node (ref "J9") (pin "5") (pinfunction "5_5") (pintype "passive"))
    )
    (net (code "91") (name "unconnected-(J9-Pad6)") (class "Default")
      (node (ref "J9") (pin "6") (pinfunction "6_6") (pintype "passive"))
    )
    (net (code "92") (name "unconnected-(J9-Pad7)") (class "Default")
      (node (ref "J9") (pin "7") (pinfunction "7_7") (pintype "passive"))
    )
    (net (code "93") (name "unconnected-(J10-Pad1)") (class "Default")
      (node (ref "J10") (pin "1") (pinfunction "1_1") (pintype "passive"))
    )
    (net (code "94") (name "unconnected-(J10-Pad2)") (class "Default")
      (node (ref "J10") (pin "2") (pinfunction "2_2") (pintype "passive"))
    )
    (net (code "95") (name "unconnected-(J10-Pad3)") (class "Default")
      (node (ref "J10") (pin "3") (pinfunction "3_3") (pintype "passive"))
    )
    (net (code "96") (name "unconnected-(J10-Pad4)") (class "Default")
      (node (ref "J10") (pin "4") (pinfunction "4_4") (pintype "passive"))
    )
    (net (code "97") (name "unconnected-(J10-Pad5)") (class "Default")
      (node (ref "J10") (pin "5") (pinfunction "5_5") (pintype "passive"))
    )
    (net (code "98") (name "unconnected-(J10-Pad6)") (class "Default")
      (node (ref "J10") (pin "6") (pinfunction "6_6") (pintype "passive"))
    )
    (net (code "99") (name "unconnected-(J10-Pad7)") (class "Default")
      (node (ref "J10") (pin "7") (pinfunction "7_7") (pintype "passive"))
    )
    (net (code "100") (name "unconnected-(J11-Pad1)") (class "Default")
      (node (ref "J11") (pin "1") (pinfunction "1_1") (pintype "passive"))
    )
    (net (code "101") (name "unconnected-(J11-Pad2)") (class "Default")
      (node (ref "J11") (pin "2") (pinfunction "2_2") (pintype "passive"))
    )
    (net (code "102") (name "unconnected-(J11-Pad3)") (class "Default")
      (node (ref "J11") (pin "3") (pinfunction "3_3") (pintype "passive"))
    )
    (net (code "103") (name "unconnected-(J11-Pad4)") (class "Default")
      (node (ref "J11") (pin "4") (pinfunction "4_4") (pintype "passive"))
    )
    (net (code "104") (name "unconnected-(J11-Pad5)") (class "Default")
      (node (ref "J11") (pin "5") (pinfunction "5_5") (pintype "passive"))
    )
    (net (code "105") (name "unconnected-(J11-Pad6)") (class "Default")
      (node (ref "J11") (pin "6") (pinfunction "6_6") (pintype "passive"))
    )
    (net (code "106") (name "unconnected-(J11-Pad7)") (class "Default")
      (node (ref "J11") (pin "7") (pinfunction "7_7") (pintype "passive"))
    )
    (net (code "107") (name "unconnected-(J11-Pad8)") (class "Default")
      (node (ref "J11") (pin "8") (pinfunction "8_8") (pintype "passive"))
    )
    (net (code "108") (name "unconnected-(J11-PadShell)") (class "Default")
      (node (ref "J11") (pin "Shell") (pinfunction "Shell_Shell") (pintype "passive"))
    )
    (net (code "109") (name "unconnected-(J12-1-Pad6)") (class "Default")
      (node (ref "J12") (pin "6") (pinfunction "1_6") (pintype "passive"))
    )
    (net (code "110") (name "unconnected-(J12-2-Pad5)") (class "Default")
      (node (ref "J12") (pin "5") (pinfunction "2_5") (pintype "passive"))
    )
    (net (code "111") (name "unconnected-(J12-3-Pad4)") (class "Default")
      (node (ref "J12") (pin "4") (pinfunction "3_4") (pintype "passive"))
    )
    (net (code "112") (name "unconnected-(J12-4-Pad3)") (class "Default")
      (node (ref "J12") (pin "3") (pinfunction "4_3") (pintype "passive"))
    )
    (net (code "113") (name "unconnected-(J12-5-Pad2)") (class "Default")
      (node (ref "J12") (pin "2") (pinfunction "5_2") (pintype "passive"))
    )
    (net (code "114") (name "unconnected-(J12-6-Pad1)") (class "Default")
      (node (ref "J12") (pin "1") (pinfunction "6_1") (pintype "passive"))
    )
    (net (code "115") (name "unconnected-(J13-1-Pad6)") (class "Default")
      (node (ref "J13") (pin "6") (pinfunction "1_6") (pintype "passive"))
    )
    (net (code "116") (name "unconnected-(J13-2-Pad5)") (class "Default")
      (node (ref "J13") (pin "5") (pinfunction "2_5") (pintype "passive"))
    )
    (net (code "117") (name "unconnected-(J13-3-Pad4)") (class "Default")
      (node (ref "J13") (pin "4") (pinfunction "3_4") (pintype "passive"))
    )
    (net (code "118") (name "unconnected-(J13-4-Pad3)") (class "Default")
      (node (ref "J13") (pin "3") (pinfunction "4_3") (pintype "passive"))
    )
    (net (code "119") (name "unconnected-(J13-5-Pad2)") (class "Default")
      (node (ref "J13") (pin "2") (pinfunction "5_2") (pintype "passive"))
    )
    (net (code "120") (name "unconnected-(J13-6-Pad1)") (class "Default")
      (node (ref "J13") (pin "1") (pinfunction "6_1") (pintype "passive"))
    )
    (net (code "121") (name "unconnected-(J14-Pad1)") (class "Default")
      (node (ref "J14") (pin "1") (pinfunction "1_1") (pintype "passive"))
    )
    (net (code "122") (name "unconnected-(J14-Pad2)") (class "Default")
      (node (ref "J14") (pin "2") (pinfunction "2_2") (pintype "passive"))
    )
    (net (code "123") (name "unconnected-(J14-Pad3)") (class "Default")
      (node (ref "J14") (pin "3") (pinfunction "3_3") (pintype "passive"))
    )
    (net (code "124") (name "unconnected-(J14-Pad4)") (class "Default")
      (node (ref "J14") (pin "4") (pinfunction "4_4") (pintype "passive"))
    )
    (net (code "125") (name "unconnected-(J14-Pad5)") (class "Default")
      (node (ref "J14") (pin "5") (pinfunction "5_5") (pintype "passive"))
    )
    (net (code "126") (name "unconnected-(J14-Pad6)") (class "Default")
      (node (ref "J14") (pin "6") (pinfunction "6_6") (pintype "passive"))
    )
    (net (code "127") (name "unconnected-(J14-Pad7)") (class "Default")
      (node (ref "J14") (pin "7") (pinfunction "7_7") (pintype "passive"))
    )
    (net (code "128") (name "unconnected-(J14-Pad8)") (class "Default")
      (node (ref "J14") (pin "8") (pinfunction "8_8") (pintype "passive"))
    )
    (net (code "129") (name "unconnected-(J14-Pad9)") (class "Default")
      (node (ref "J14") (pin "9") (pinfunction "9_9") (pintype "passive"))
    )
    (net (code "130") (name "unconnected-(J14-Pad10)") (class "Default")
      (node (ref "J14") (pin "10") (pinfunction "10_10") (pintype "passive"))
    )
    (net (code "131") (name "unconnected-(J16-Pad1)") (class "Default")
      (node (ref "J16") (pin "1") (pinfunction "1_1") (pintype "passive"))
    )
    (net (code "132") (name "unconnected-(J16-Pad2)") (class "Default")
      (node (ref "J16") (pin "2") (pinfunction "2_2") (pintype "passive"))
    )
    (net (code "133") (name "unconnected-(J16-Pad3)") (class "Default")
      (node (ref "J16") (pin "3") (pinfunction "3_3") (pintype "passive"))
    )
    (net (code "134") (name "unconnected-(J16-Pad4)") (class "Default")
      (node (ref "J16") (pin "4") (pinfunction "4_4") (pintype "passive"))
    )
    (net (code "135") (name "unconnected-(J16-Pad5)") (class "Default")
      (node (ref "J16") (pin "5") (pinfunction "5_5") (pintype "passive"))
    )
    (net (code "136") (name "unconnected-(J16-Pad6)") (class "Default")
      (node (ref "J16") (pin "6") (pinfunction "6_6") (pintype "passive"))
    )
    (net (code "137") (name "unconnected-(J16-Pad7)") (class "Default")
      (node (ref "J16") (pin "7") (pinfunction "7_7") (pintype "passive"))
    )
    (net (code "138") (name "unconnected-(J16-Pad8)") (class "Default")
      (node (ref "J16") (pin "8") (pinfunction "8_8") (pintype "passive"))
    )
    (net (code "139") (name "unconnected-(J16-Pad9)") (class "Default")
      (node (ref "J16") (pin "9") (pinfunction "9_9") (pintype "passive"))
    )
    (net (code "140") (name "unconnected-(J16-Pad10)") (class "Default")
      (node (ref "J16") (pin "10") (pinfunction "10_10") (pintype "passive"))
    )
    (net (code "141") (name "unconnected-(U1-ASSOC{slash}DIO5{slash}PTD4-Pad15)") (class "Default")
      (node (ref "U1") (pin "15") (pinfunction "ASSOC/DIO5/PTD4_15") (pintype "passive"))
    )
    (net (code "142") (name "unconnected-(U1-BKGD{slash}PTA4-Pad8)") (class "Default")
      (node (ref "U1") (pin "8") (pinfunction "BKGD/PTA4_8") (pintype "passive"))
    )
    (net (code "143") (name "unconnected-(U1-DIN{slash}PTB0-Pad3)") (class "Default")
      (node (ref "U1") (pin "3") (pinfunction "DIN/PTB0_3") (pintype "passive"))
    )
    (net (code "144") (name "unconnected-(U1-DIO0{slash}ADC0{slash}PTA0-Pad20)") (class "Default")
      (node (ref "U1") (pin "20") (pinfunction "DIO0/ADC0/PTA0_20") (pintype "passive"))
    )
    (net (code "145") (name "unconnected-(U1-DIO1{slash}ADC1{slash}PTA3{slash}SCL-Pad19)") (class "Default")
      (node (ref "U1") (pin "19") (pinfunction "DIO1/ADC1/PTA3/SCL_19") (pintype "passive"))
    )
    (net (code "146") (name "unconnected-(U1-DIO2{slash}ADC2{slash}PTB2{slash}SPSCK-Pad18)") (class "Default")
      (node (ref "U1") (pin "18") (pinfunction "DIO2/ADC2/PTB2/SPSCK_18") (pintype "passive"))
    )
    (net (code "147") (name "unconnected-(U1-DIO3{slash}ADC3{slash}PTB5,A7{slash}~{SS}-Pad17)") (class "Default")
      (node (ref "U1") (pin "17") (pinfunction "DIO3/ADC3/PTB5,A7/~{SS}_17") (pintype "passive"))
    )
    (net (code "148") (name "unconnected-(U1-DIO4{slash}PTB3{slash}MOSI1-Pad11)") (class "Default")
      (node (ref "U1") (pin "11") (pinfunction "DIO4/PTB3/MOSI1_11") (pintype "passive"))
    )
    (net (code "149") (name "unconnected-(U1-DIO11{slash}PWM1{slash}PTA2{slash}SDA-Pad7)") (class "Default")
      (node (ref "U1") (pin "7") (pinfunction "DIO11/PWM1/PTA2/SDA_7") (pintype "passive"))
    )
    (net (code "150") (name "unconnected-(U1-DIO12{slash}PTB4{slash}MISO1-Pad4)") (class "Default")
      (node (ref "U1") (pin "4") (pinfunction "DIO12/PTB4/MISO1_4") (pintype "passive"))
    )
    (net (code "151") (name "unconnected-(U1-DOUT{slash}PTB1-Pad2)") (class "Default")
      (node (ref "U1") (pin "2") (pinfunction "DOUT/PTB1_2") (pintype "passive"))
    )
    (net (code "152") (name "unconnected-(U1-GND-Pad10)") (class "Default")
      (node (ref "U1") (pin "10") (pinfunction "GND_10") (pintype "passive"))
    )
    (net (code "153") (name "unconnected-(U1-ON{slash}~{SLEEP}{slash}PTA1-Pad13)") (class "Default")
      (node (ref "U1") (pin "13") (pinfunction "ON/~{SLEEP}/PTA1_13") (pintype "passive"))
    )
    (net (code "154") (name "unconnected-(U1-RSSI{slash}DIO10{slash}PWM0{slash}PTC5-Pad6)") (class "Default")
      (node (ref "U1") (pin "6") (pinfunction "RSSI/DIO10/PWM0/PTC5_6") (pintype "passive"))
    )
    (net (code "155") (name "unconnected-(U1-SLEEP_RQ{slash}~{DTR}{slash}PTD5-Pad9)") (class "Default")
      (node (ref "U1") (pin "9") (pinfunction "SLEEP_RQ/~{DTR}/PTD5_9") (pintype "passive"))
    )
    (net (code "156") (name "unconnected-(U1-VCC-Pad1)") (class "Default")
      (node (ref "U1") (pin "1") (pinfunction "VCC_1") (pintype "passive"))
    )
    (net (code "157") (name "unconnected-(U1-VREF-Pad14)") (class "Default")
      (node (ref "U1") (pin "14") (pinfunction "VREF_14") (pintype "passive"))
    )
    (net (code "158") (name "unconnected-(U1-~{CTS}{slash}DIO7{slash}PTC0-Pad12)") (class "Default")
      (node (ref "U1") (pin "12") (pinfunction "~{CTS}/DIO7/PTC0_12") (pintype "passive"))
    )
    (net (code "159") (name "unconnected-(U1-~{RESET}{slash}PTA5-Pad5)") (class "Default")
      (node (ref "U1") (pin "5") (pinfunction "~{RESET}/PTA5_5") (pintype "passive"))
    )
    (net (code "160") (name "unconnected-(U1-~{RT}S{slash}DIO6{slash}PTD7-Pad16)") (class "Default")
      (node (ref "U1") (pin "16") (pinfunction "~{RT}S/DIO6/PTD7_16") (pintype "passive"))
    )
    (net (code "161") (name "unconnected-(U2-3V3-Pad1)") (class "Default")
      (node (ref "U2") (pin "1") (pinfunction "3V3_1") (pintype "passive"))
    )
    (net (code "162") (name "unconnected-(U2-5V-Pad14)") (class "Default")
      (node (ref "U2") (pin "14") (pinfunction "5V_14") (pintype "passive"))
    )
    (net (code "163") (name "unconnected-(U2-GND-Pad15)") (class "Default")
      (node (ref "U2") (pin "15") (pinfunction "GND_15") (pintype "passive"))
    )
    (net (code "164") (name "unconnected-(U2-GND-Pad18)") (class "Default")
      (node (ref "U2") (pin "18") (pinfunction "GND_18") (pintype "passive"))
    )
    (net (code "165") (name "unconnected-(U2-GND-Pad21)") (class "Default")
      (node (ref "U2") (pin "21") (pinfunction "GND_21") (pintype "passive"))
    )
    (net (code "166") (name "unconnected-(U2-GND-Pad32)") (class "Default")
      (node (ref "U2") (pin "32") (pinfunction "GND_32") (pintype "passive"))
    )
    (net (code "167") (name "unconnected-(U2-GPIO0-Pad7)") (class "Default")
      (node (ref "U2") (pin "7") (pinfunction "GPIO0_7") (pintype "passive"))
    )
    (net (code "168") (name "unconnected-(U2-GPIO1-Pad8)") (class "Default")
      (node (ref "U2") (pin "8") (pinfunction "GPIO1_8") (pintype "passive"))
    )
    (net (code "169") (name "unconnected-(U2-GPIO2-Pad12)") (class "Default")
      (node (ref "U2") (pin "12") (pinfunction "GPIO2_12") (pintype "passive"))
    )
    (net (code "170") (name "unconnected-(U2-GPIO3-Pad13)") (class "Default")
      (node (ref "U2") (pin "13") (pinfunction "GPIO3_13") (pintype "passive"))
    )
    (net (code "171") (name "unconnected-(U2-GPIO4-Pad3)") (class "Default")
      (node (ref "U2") (pin "3") (pinfunction "GPIO4_3") (pintype "passive"))
    )
    (net (code "172") (name "unconnected-(U2-GPIO5-Pad4)") (class "Default")
      (node (ref "U2") (pin "4") (pinfunction "GPIO5_4") (pintype "passive"))
    )
    (net (code "173") (name "unconnected-(U2-GPIO6-Pad5)") (class "Default")
      (node (ref "U2") (pin "5") (pinfunction "GPIO6_5") (pintype "passive"))
    )
    (net (code "174") (name "unconnected-(U2-GPIO7-Pad6)") (class "Default")
      (node (ref "U2") (pin "6") (pinfunction "GPIO7_6") (pintype "passive"))
    )
    (net (code "175") (name "unconnected-(U2-GPIO8-Pad9)") (class "Default")
      (node (ref "U2") (pin "9") (pinfunction "GPIO8_9") (pintype "passive"))
    )
    (net (code "176") (name "unconnected-(U2-GPIO9-Pad22)") (class "Default")
      (node (ref "U2") (pin "22") (pinfunction "GPIO9_22") (pintype "passive"))
    )
    (net (code "177") (name "unconnected-(U2-GPIO10-Pad10)") (class "Default")
      (node (ref "U2") (pin "10") (pinfunction "GPIO10_10") (pintype "passive"))
    )
    (net (code "178") (name "unconnected-(U2-GPIO11-Pad11)") (class "Default")
      (node (ref "U2") (pin "11") (pinfunction "GPIO11_11") (pintype "passive"))
    )
    (net (code "179") (name "unconnected-(U2-GPIO12-Pad19)") (class "Default")
      (node (ref "U2") (pin "19") (pinfunction "GPIO12_19") (pintype "passive"))
    )
    (net (code "180") (name "unconnected-(U2-GPIO13-Pad20)") (class "Default")
      (node (ref "U2") (pin "20") (pinfunction "GPIO13_20") (pintype "passive"))
    )
    (net (code "181") (name "unconnected-(U2-GPIO15-Pad29)") (class "Default")
      (node (ref "U2") (pin "29") (pinfunction "GPIO15_29") (pintype "passive"))
    )
    (net (code "182") (name "unconnected-(U2-GPIO18-Pad23)") (class "Default")
      (node (ref "U2") (pin "23") (pinfunction "GPIO18_23") (pintype "passive"))
    )
    (net (code "183") (name "unconnected-(U2-GPIO19-Pad24)") (class "Default")
      (node (ref "U2") (pin "24") (pinfunction "GPIO19_24") (pintype "passive"))
    )
    (net (code "184") (name "unconnected-(U2-GPIO20-Pad25)") (class "Default")
      (node (ref "U2") (pin "25") (pinfunction "GPIO20_25") (pintype "passive"))
    )
    (net (code "185") (name "unconnected-(U2-GPIO21-Pad26)") (class "Default")
      (node (ref "U2") (pin "26") (pinfunction "GPIO21_26") (pintype "passive"))
    )
    (net (code "186") (name "unconnected-(U2-GPIO22-Pad27)") (class "Default")
      (node (ref "U2") (pin "27") (pinfunction "GPIO22_27") (pintype "passive"))
    )
    (net (code "187") (name "unconnected-(U2-GPIO23-Pad28)") (class "Default")
      (node (ref "U2") (pin "28") (pinfunction "GPIO23_28") (pintype "passive"))
    )
    (net (code "188") (name "unconnected-(U2-NC-Pad16)") (class "Default")
      (node (ref "U2") (pin "16") (pinfunction "NC_16") (pintype "passive"))
    )
    (net (code "189") (name "unconnected-(U2-NC-Pad17)") (class "Default")
      (node (ref "U2") (pin "17") (pinfunction "NC_17") (pintype "passive"))
    )
    (net (code "190") (name "unconnected-(U2-RST-Pad2)") (class "Default")
      (node (ref "U2") (pin "2") (pinfunction "RST_2") (pintype "passive"))
    )
    (net (code "191") (name "unconnected-(U2-RX-Pad30)") (class "Default")
      (node (ref "U2") (pin "30") (pinfunction "RX_30") (pintype "passive"))
    )
    (net (code "192") (name "unconnected-(U2-TX-Pad31)") (class "Default")
      (node (ref "U2") (pin "31") (pinfunction "TX_31") (pintype "passive"))
    )
    (net (code "193") (name "unconnected-(U3-RO-Pad1)") (class "Default")
      (node (ref "U3") (pin "1") (pinfunction "RO_1") (pintype "passive"))
    )
    (net (code "194") (name "unconnected-(U4-NC-Pad1)") (class "Default")
      (node (ref "U4") (pin "1") (pinfunction "NC_1") (pintype "passive"))
    )
    (net (code "195") (name "unconnected-(U4-NC-Pad4)") (class "Default")
      (node (ref "U4") (pin "4") (pinfunction "NC_4") (pintype "passive"))
    )
  )
)
